# Analog_Modulation_and_Supply.net
KiCad netlist of a schematic drawn in Altium Designer
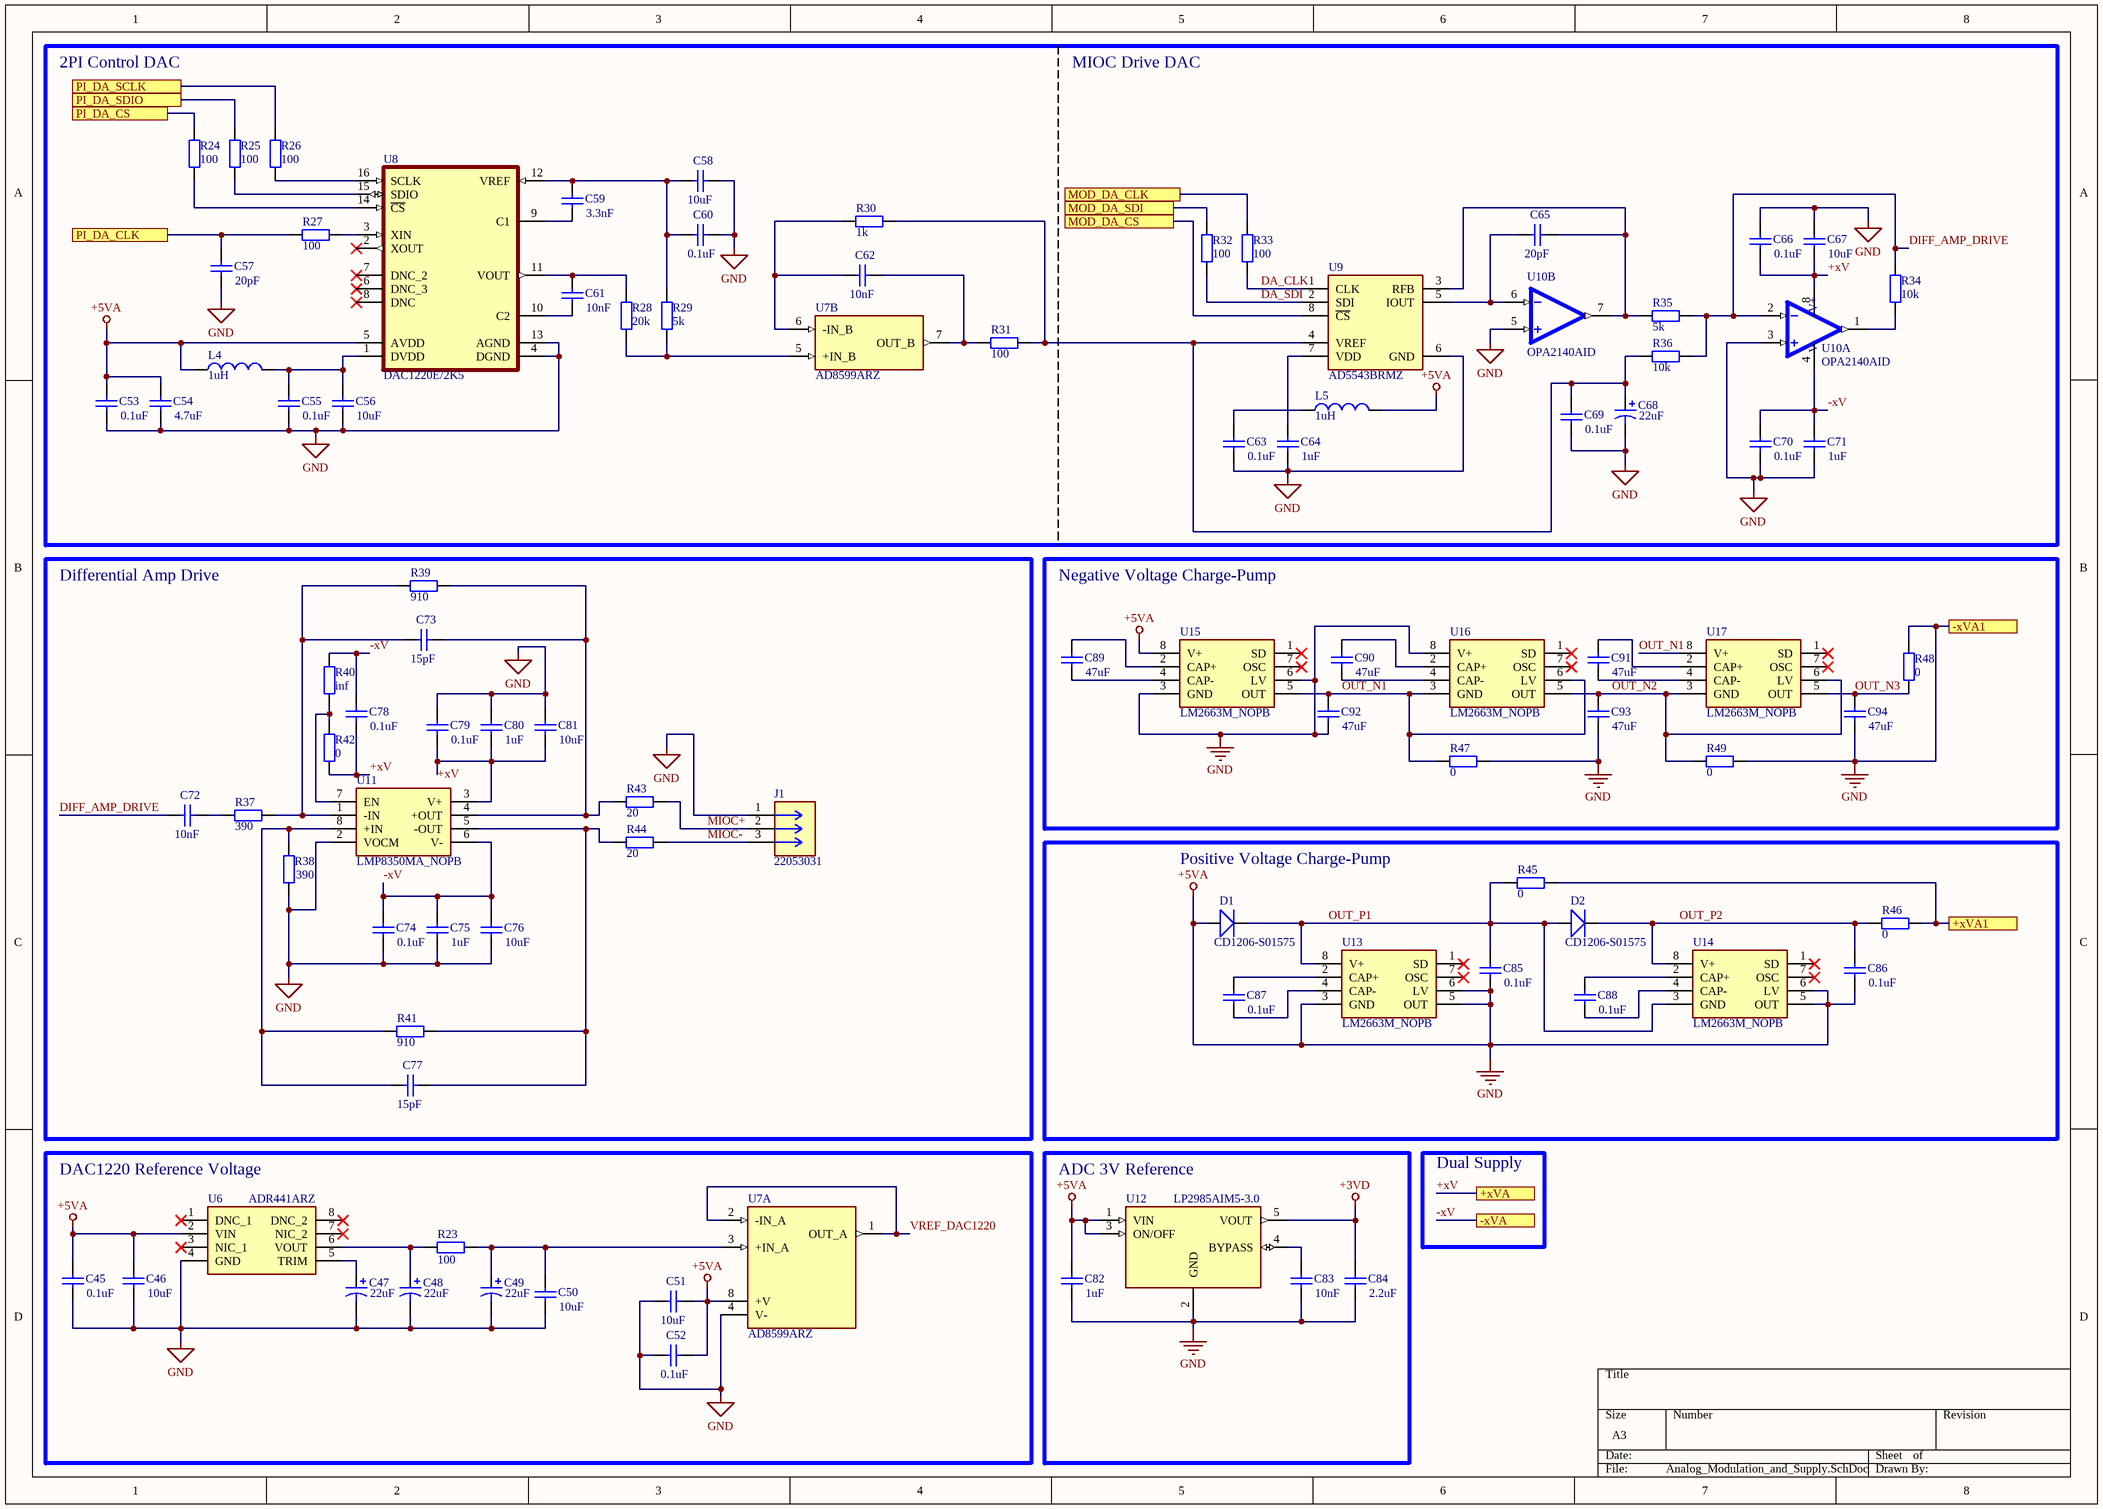
[diagram p0: Analog_Modulation_and_Supply.SchDoc]

(export (version "E")
  (design (tool "Eeschema 10.0.6"))
  (components
    (comp (ref "C45")
      (value "0.1uF")
      (footprint "RAD-0.3")
      (description "Capacitor")
      (fields (field (name "Comment") "Cap") (field (name "PUBLISHER") "Altium Limited"))
      (libsource (lib "Miscellaneous Devices") (part "Cap"))
    )
    (comp (ref "C46")
      (value "10uF")
      (footprint "RAD-0.3")
      (description "Capacitor")
      (fields (field (name "Comment") "Cap") (field (name "PUBLISHER") "Altium Limited"))
      (libsource (lib "Miscellaneous Devices") (part "Cap"))
    )
    (comp (ref "C47")
      (value "22uF")
      (footprint "RB7.6-15")
      (description "Polarized Capacitor (Radial)")
      (fields (field (name "Comment") "Cap Pol1") (field (name "PUBLISHER") "Altium Limited"))
      (libsource (lib "Miscellaneous Devices") (part "Cap Pol1"))
    )
    (comp (ref "C48")
      (value "22uF")
      (footprint "RB7.6-15")
      (description "Polarized Capacitor (Radial)")
      (fields (field (name "Comment") "Cap Pol1") (field (name "PUBLISHER") "Altium Limited"))
      (libsource (lib "Miscellaneous Devices") (part "Cap Pol1"))
    )
    (comp (ref "C49")
      (value "22uF")
      (footprint "RB7.6-15")
      (description "Polarized Capacitor (Radial)")
      (fields (field (name "Comment") "Cap Pol1") (field (name "PUBLISHER") "Altium Limited"))
      (libsource (lib "Miscellaneous Devices") (part "Cap Pol1"))
    )
    (comp (ref "C50")
      (value "10uF")
      (footprint "RAD-0.3")
      (description "Capacitor")
      (fields (field (name "Comment") "Cap") (field (name "PUBLISHER") "Altium Limited"))
      (libsource (lib "Miscellaneous Devices") (part "Cap"))
    )
    (comp (ref "C51")
      (value "10uF")
      (footprint "RAD-0.3")
      (description "Capacitor")
      (fields (field (name "Comment") "Cap") (field (name "PUBLISHER") "Altium Limited"))
      (libsource (lib "Miscellaneous Devices") (part "Cap"))
    )
    (comp (ref "C52")
      (value "0.1uF")
      (footprint "RAD-0.3")
      (description "Capacitor")
      (fields (field (name "Comment") "Cap") (field (name "PUBLISHER") "Altium Limited"))
      (libsource (lib "Miscellaneous Devices") (part "Cap"))
    )
    (comp (ref "C53")
      (value "0.1uF")
      (footprint "RAD-0.3")
      (description "Capacitor")
      (fields (field (name "Comment") "Cap") (field (name "PUBLISHER") "Altium Limited"))
      (libsource (lib "Miscellaneous Devices") (part "Cap"))
    )
    (comp (ref "C54")
      (value "4.7uF")
      (footprint "RAD-0.3")
      (description "Capacitor")
      (fields (field (name "Comment") "Cap") (field (name "PUBLISHER") "Altium Limited"))
      (libsource (lib "Miscellaneous Devices") (part "Cap"))
    )
    (comp (ref "C55")
      (value "0.1uF")
      (footprint "RAD-0.3")
      (description "Capacitor")
      (fields (field (name "Comment") "Cap") (field (name "PUBLISHER") "Altium Limited"))
      (libsource (lib "Miscellaneous Devices") (part "Cap"))
    )
    (comp (ref "C56")
      (value "10uF")
      (footprint "RAD-0.3")
      (description "Capacitor")
      (fields (field (name "Comment") "Cap") (field (name "PUBLISHER") "Altium Limited"))
      (libsource (lib "Miscellaneous Devices") (part "Cap"))
    )
    (comp (ref "C57")
      (value "20pF")
      (footprint "RAD-0.3")
      (description "Capacitor")
      (fields (field (name "Comment") "Cap") (field (name "PUBLISHER") "Altium Limited"))
      (libsource (lib "Miscellaneous Devices") (part "Cap"))
    )
    (comp (ref "C58")
      (value "10uF")
      (footprint "RAD-0.3")
      (description "Capacitor")
      (fields (field (name "Comment") "Cap") (field (name "PUBLISHER") "Altium Limited"))
      (libsource (lib "Miscellaneous Devices") (part "Cap"))
    )
    (comp (ref "C59")
      (value "3.3nF")
      (footprint "RAD-0.3")
      (description "Capacitor")
      (fields (field (name "Comment") "Cap") (field (name "PUBLISHER") "Altium Limited"))
      (libsource (lib "Miscellaneous Devices") (part "Cap"))
    )
    (comp (ref "C60")
      (value "0.1uF")
      (footprint "RAD-0.3")
      (description "Capacitor")
      (fields (field (name "Comment") "Cap") (field (name "PUBLISHER") "Altium Limited"))
      (libsource (lib "Miscellaneous Devices") (part "Cap"))
    )
    (comp (ref "C61")
      (value "10nF")
      (footprint "RAD-0.3")
      (description "Capacitor")
      (fields (field (name "Comment") "Cap") (field (name "PUBLISHER") "Altium Limited"))
      (libsource (lib "Miscellaneous Devices") (part "Cap"))
    )
    (comp (ref "C62")
      (value "10nF")
      (footprint "RAD-0.3")
      (description "Capacitor")
      (fields (field (name "Comment") "Cap") (field (name "PUBLISHER") "Altium Limited"))
      (libsource (lib "Miscellaneous Devices") (part "Cap"))
    )
    (comp (ref "C63")
      (value "0.1uF")
      (footprint "RAD-0.3")
      (description "Capacitor")
      (fields (field (name "Comment") "Cap") (field (name "PUBLISHER") "Altium Limited"))
      (libsource (lib "Miscellaneous Devices") (part "Cap"))
    )
    (comp (ref "C64")
      (value "1uF")
      (footprint "RAD-0.3")
      (description "Capacitor")
      (fields (field (name "Comment") "Cap") (field (name "PUBLISHER") "Altium Limited"))
      (libsource (lib "Miscellaneous Devices") (part "Cap"))
    )
    (comp (ref "C65")
      (value "20pF")
      (footprint "RAD-0.3")
      (description "Capacitor")
      (fields (field (name "Comment") "Cap") (field (name "PUBLISHER") "Altium Limited"))
      (libsource (lib "Miscellaneous Devices") (part "Cap"))
    )
    (comp (ref "C66")
      (value "0.1uF")
      (footprint "RAD-0.3")
      (description "Capacitor")
      (fields (field (name "Comment") "Cap") (field (name "PUBLISHER") "Altium Limited"))
      (libsource (lib "Miscellaneous Devices") (part "Cap"))
    )
    (comp (ref "C67")
      (value "10uF")
      (footprint "RAD-0.3")
      (description "Capacitor")
      (fields (field (name "Comment") "Cap") (field (name "PUBLISHER") "Altium Limited"))
      (libsource (lib "Miscellaneous Devices") (part "Cap"))
    )
    (comp (ref "C68")
      (value "22uF")
      (footprint "RB7.6-15")
      (description "Polarized Capacitor (Radial)")
      (fields (field (name "Comment") "Cap Pol1") (field (name "PUBLISHER") "Altium Limited"))
      (libsource (lib "Miscellaneous Devices") (part "Cap Pol1"))
    )
    (comp (ref "C69")
      (value "0.1uF")
      (footprint "RAD-0.3")
      (description "Capacitor")
      (fields (field (name "Comment") "Cap") (field (name "PUBLISHER") "Altium Limited"))
      (libsource (lib "Miscellaneous Devices") (part "Cap"))
    )
    (comp (ref "C70")
      (value "0.1uF")
      (footprint "RAD-0.3")
      (description "Capacitor")
      (fields (field (name "Comment") "Cap") (field (name "PUBLISHER") "Altium Limited"))
      (libsource (lib "Miscellaneous Devices") (part "Cap"))
    )
    (comp (ref "C71")
      (value "1uF")
      (footprint "RAD-0.3")
      (description "Capacitor")
      (fields (field (name "Comment") "Cap") (field (name "PUBLISHER") "Altium Limited"))
      (libsource (lib "Miscellaneous Devices") (part "Cap"))
    )
    (comp (ref "C72")
      (value "10nF")
      (footprint "RAD-0.3")
      (description "Capacitor")
      (fields (field (name "Comment") "Cap") (field (name "PUBLISHER") "Altium Limited"))
      (libsource (lib "Miscellaneous Devices") (part "Cap"))
    )
    (comp (ref "C73")
      (value "15pF")
      (footprint "RAD-0.3")
      (description "Capacitor")
      (fields (field (name "Comment") "Cap") (field (name "PUBLISHER") "Altium Limited"))
      (libsource (lib "Miscellaneous Devices") (part "Cap"))
    )
    (comp (ref "C74")
      (value "0.1uF")
      (footprint "RAD-0.3")
      (description "Capacitor")
      (fields (field (name "Comment") "Cap") (field (name "PUBLISHER") "Altium Limited"))
      (libsource (lib "Miscellaneous Devices") (part "Cap"))
    )
    (comp (ref "C75")
      (value "1uF")
      (footprint "RAD-0.3")
      (description "Capacitor")
      (fields (field (name "Comment") "Cap") (field (name "PUBLISHER") "Altium Limited"))
      (libsource (lib "Miscellaneous Devices") (part "Cap"))
    )
    (comp (ref "C76")
      (value "10uF")
      (footprint "RAD-0.3")
      (description "Capacitor")
      (fields (field (name "Comment") "Cap") (field (name "PUBLISHER") "Altium Limited"))
      (libsource (lib "Miscellaneous Devices") (part "Cap"))
    )
    (comp (ref "C77")
      (value "15pF")
      (footprint "RAD-0.3")
      (description "Capacitor")
      (fields (field (name "Comment") "Cap") (field (name "PUBLISHER") "Altium Limited"))
      (libsource (lib "Miscellaneous Devices") (part "Cap"))
    )
    (comp (ref "C78")
      (value "0.1uF")
      (footprint "RAD-0.3")
      (description "Capacitor")
      (fields (field (name "Comment") "Cap") (field (name "PUBLISHER") "Altium Limited"))
      (libsource (lib "Miscellaneous Devices") (part "Cap"))
    )
    (comp (ref "C79")
      (value "0.1uF")
      (footprint "RAD-0.3")
      (description "Capacitor")
      (fields (field (name "Comment") "Cap") (field (name "PUBLISHER") "Altium Limited"))
      (libsource (lib "Miscellaneous Devices") (part "Cap"))
    )
    (comp (ref "C80")
      (value "1uF")
      (footprint "RAD-0.3")
      (description "Capacitor")
      (fields (field (name "Comment") "Cap") (field (name "PUBLISHER") "Altium Limited"))
      (libsource (lib "Miscellaneous Devices") (part "Cap"))
    )
    (comp (ref "C81")
      (value "10uF")
      (footprint "RAD-0.3")
      (description "Capacitor")
      (fields (field (name "Comment") "Cap") (field (name "PUBLISHER") "Altium Limited"))
      (libsource (lib "Miscellaneous Devices") (part "Cap"))
    )
    (comp (ref "C82")
      (value "1uF")
      (footprint "RAD-0.3")
      (description "Capacitor")
      (fields (field (name "Comment") "Cap") (field (name "PUBLISHER") "Altium Limited"))
      (libsource (lib "Miscellaneous Devices") (part "Cap"))
    )
    (comp (ref "C83")
      (value "10nF")
      (footprint "RAD-0.3")
      (description "Capacitor")
      (fields (field (name "Comment") "Cap") (field (name "PUBLISHER") "Altium Limited"))
      (libsource (lib "Miscellaneous Devices") (part "Cap"))
    )
    (comp (ref "C84")
      (value "2.2uF")
      (footprint "RAD-0.3")
      (description "Capacitor")
      (fields (field (name "Comment") "Cap") (field (name "PUBLISHER") "Altium Limited"))
      (libsource (lib "Miscellaneous Devices") (part "Cap"))
    )
    (comp (ref "C85")
      (value "0.1uF")
      (footprint "RAD-0.3")
      (description "Capacitor")
      (fields (field (name "Comment") "Cap") (field (name "PUBLISHER") "Altium Limited"))
      (libsource (lib "Miscellaneous Devices") (part "Cap"))
    )
    (comp (ref "C86")
      (value "0.1uF")
      (footprint "RAD-0.3")
      (description "Capacitor")
      (fields (field (name "Comment") "Cap") (field (name "PUBLISHER") "Altium Limited"))
      (libsource (lib "Miscellaneous Devices") (part "Cap"))
    )
    (comp (ref "C87")
      (value "0.1uF")
      (footprint "RAD-0.3")
      (description "Capacitor")
      (fields (field (name "Comment") "Cap") (field (name "PUBLISHER") "Altium Limited"))
      (libsource (lib "Miscellaneous Devices") (part "Cap"))
    )
    (comp (ref "C88")
      (value "0.1uF")
      (footprint "RAD-0.3")
      (description "Capacitor")
      (fields (field (name "Comment") "Cap") (field (name "PUBLISHER") "Altium Limited"))
      (libsource (lib "Miscellaneous Devices") (part "Cap"))
    )
    (comp (ref "C89")
      (value "47uF")
      (footprint "RAD-0.3")
      (description "Capacitor")
      (fields (field (name "Comment") "Cap") (field (name "PUBLISHER") "Altium Limited"))
      (libsource (lib "Miscellaneous Devices") (part "Cap"))
    )
    (comp (ref "C90")
      (value "47uF")
      (footprint "RAD-0.3")
      (description "Capacitor")
      (fields (field (name "Comment") "Cap") (field (name "PUBLISHER") "Altium Limited"))
      (libsource (lib "Miscellaneous Devices") (part "Cap"))
    )
    (comp (ref "C91")
      (value "47uF")
      (footprint "RAD-0.3")
      (description "Capacitor")
      (fields (field (name "Comment") "Cap") (field (name "PUBLISHER") "Altium Limited"))
      (libsource (lib "Miscellaneous Devices") (part "Cap"))
    )
    (comp (ref "C92")
      (value "47uF")
      (footprint "RAD-0.3")
      (description "Capacitor")
      (fields (field (name "Comment") "Cap") (field (name "PUBLISHER") "Altium Limited"))
      (libsource (lib "Miscellaneous Devices") (part "Cap"))
    )
    (comp (ref "C93")
      (value "47uF")
      (footprint "RAD-0.3")
      (description "Capacitor")
      (fields (field (name "Comment") "Cap") (field (name "PUBLISHER") "Altium Limited"))
      (libsource (lib "Miscellaneous Devices") (part "Cap"))
    )
    (comp (ref "C94")
      (value "47uF")
      (footprint "RAD-0.3")
      (description "Capacitor")
      (fields (field (name "Comment") "Cap") (field (name "PUBLISHER") "Altium Limited"))
      (libsource (lib "Miscellaneous Devices") (part "Cap"))
    )
    (comp (ref "D1")
      (value "CD1206-S01575")
      (footprint "LED-1206")
      (description "CD1206-S01575, SMT Switching Diode, Vr=75V 150mA, 4ns, 2-Pin 1206 ¦ Bourns CD1206-S01575")
      (fields (field (name "MF") "Bourns"))
      (libsource (lib "Lib_Schematic_Gyro_Single_Axis") (part "CD1206-S01575"))
    )
    (comp (ref "D2")
      (value "CD1206-S01575")
      (footprint "LED-1206")
      (description "CD1206-S01575, SMT Switching Diode, Vr=75V 150mA, 4ns, 2-Pin 1206 ¦ Bourns CD1206-S01575")
      (fields (field (name "MF") "Bourns"))
      (libsource (lib "Lib_Schematic_Gyro_Single_Axis") (part "CD1206-S01575"))
    )
    (comp (ref "J1")
      (value "22053031")
      (footprint "22-05-3031")
      (description "Headers R/A PCB HDR 3P TIN FRICTION LOCK ¦ Molex Incorporated 22-05-3031")
      (fields (field (name "MF") "Molex") (field (name "MP") "22-05-3031"))
      (libsource (lib "Lib_Schematic_Gyro_Single_Axis") (part "22053031"))
    )
    (comp (ref "L4")
      (value "1uH")
      (footprint "0402-A")
      (description "Inductor")
      (fields (field (name "PUBLISHER") "Altium Limited"))
      (libsource (lib "Miscellaneous Devices") (part "Inductor"))
    )
    (comp (ref "L5")
      (value "1uH")
      (footprint "0402-A")
      (description "Inductor")
      (fields (field (name "PUBLISHER") "Altium Limited"))
      (libsource (lib "Miscellaneous Devices") (part "Inductor"))
    )
    (comp (ref "R23")
      (value "100")
      (footprint "AXIAL-0.4")
      (description "Resistor")
      (fields (field (name "Comment") "Res2") (field (name "PUBLISHER") "Altium Limited"))
      (libsource (lib "") (part "Res2_3"))
    )
    (comp (ref "R24")
      (value "100")
      (footprint "AXIAL-0.4")
      (description "Resistor")
      (fields (field (name "Comment") "Res2") (field (name "PUBLISHER") "Altium Limited"))
      (libsource (lib "") (part "Res2_1"))
    )
    (comp (ref "R25")
      (value "100")
      (footprint "AXIAL-0.4")
      (description "Resistor")
      (fields (field (name "Comment") "Res2") (field (name "PUBLISHER") "Altium Limited"))
      (libsource (lib "") (part "Res2_1"))
    )
    (comp (ref "R26")
      (value "100")
      (footprint "AXIAL-0.4")
      (description "Resistor")
      (fields (field (name "Comment") "Res2") (field (name "PUBLISHER") "Altium Limited"))
      (libsource (lib "") (part "Res2_1"))
    )
    (comp (ref "R27")
      (value "100")
      (footprint "AXIAL-0.4")
      (description "Resistor")
      (fields (field (name "Comment") "Res2") (field (name "PUBLISHER") "Altium Limited"))
      (libsource (lib "Miscellaneous Devices") (part "Res2"))
    )
    (comp (ref "R28")
      (value "20k")
      (footprint "AXIAL-0.4")
      (description "Resistor")
      (fields (field (name "Comment") "Res2") (field (name "PUBLISHER") "Altium Limited"))
      (libsource (lib "") (part "Res2_1"))
    )
    (comp (ref "R29")
      (value "5k")
      (footprint "AXIAL-0.4")
      (description "Resistor")
      (fields (field (name "Comment") "Res2") (field (name "PUBLISHER") "Altium Limited"))
      (libsource (lib "") (part "Res2_1"))
    )
    (comp (ref "R30")
      (value "1k")
      (footprint "AXIAL-0.4")
      (description "Resistor")
      (fields (field (name "Comment") "Res2") (field (name "PUBLISHER") "Altium Limited"))
      (libsource (lib "Miscellaneous Devices") (part "Res2"))
    )
    (comp (ref "R31")
      (value "100")
      (footprint "AXIAL-0.4")
      (description "Resistor")
      (fields (field (name "Comment") "Res2") (field (name "PUBLISHER") "Altium Limited"))
      (libsource (lib "Miscellaneous Devices") (part "Res2"))
    )
    (comp (ref "R32")
      (value "100")
      (footprint "AXIAL-0.4")
      (description "Resistor")
      (fields (field (name "Comment") "Res2") (field (name "PUBLISHER") "Altium Limited"))
      (libsource (lib "") (part "Res2_2"))
    )
    (comp (ref "R33")
      (value "100")
      (footprint "AXIAL-0.4")
      (description "Resistor")
      (fields (field (name "Comment") "Res2") (field (name "PUBLISHER") "Altium Limited"))
      (libsource (lib "") (part "Res2_2"))
    )
    (comp (ref "R34")
      (value "10k")
      (footprint "AXIAL-0.4")
      (description "Resistor")
      (fields (field (name "Comment") "Res2") (field (name "PUBLISHER") "Altium Limited"))
      (libsource (lib "") (part "Res2_2"))
    )
    (comp (ref "R35")
      (value "5k")
      (footprint "AXIAL-0.4")
      (description "Resistor")
      (fields (field (name "Comment") "Res2") (field (name "PUBLISHER") "Altium Limited"))
      (libsource (lib "Miscellaneous Devices") (part "Res2"))
    )
    (comp (ref "R36")
      (value "10k")
      (footprint "AXIAL-0.4")
      (description "Resistor")
      (fields (field (name "Comment") "Res2") (field (name "PUBLISHER") "Altium Limited"))
      (libsource (lib "Miscellaneous Devices") (part "Res2"))
    )
    (comp (ref "R37")
      (value "390")
      (footprint "AXIAL-0.4")
      (description "Resistor")
      (fields (field (name "Comment") "Res2") (field (name "PUBLISHER") "Altium Limited"))
      (libsource (lib "Miscellaneous Devices") (part "Res2"))
    )
    (comp (ref "R38")
      (value "390")
      (footprint "AXIAL-0.4")
      (description "Resistor")
      (fields (field (name "Comment") "Res2") (field (name "PUBLISHER") "Altium Limited"))
      (libsource (lib "") (part "Res2_2"))
    )
    (comp (ref "R39")
      (value "910")
      (footprint "AXIAL-0.4")
      (description "Resistor")
      (fields (field (name "Comment") "Res2") (field (name "PUBLISHER") "Altium Limited"))
      (libsource (lib "Miscellaneous Devices") (part "Res2"))
    )
    (comp (ref "R40")
      (value "inf")
      (footprint "AXIAL-0.4")
      (description "Resistor")
      (fields (field (name "Comment") "Res2") (field (name "PUBLISHER") "Altium Limited"))
      (libsource (lib "") (part "Res2_2"))
    )
    (comp (ref "R41")
      (value "910")
      (footprint "AXIAL-0.4")
      (description "Resistor")
      (fields (field (name "Comment") "Res2") (field (name "PUBLISHER") "Altium Limited"))
      (libsource (lib "Miscellaneous Devices") (part "Res2"))
    )
    (comp (ref "R42")
      (value "0")
      (footprint "AXIAL-0.4")
      (description "Resistor")
      (fields (field (name "Comment") "Res2") (field (name "PUBLISHER") "Altium Limited"))
      (libsource (lib "") (part "Res2_2"))
    )
    (comp (ref "R43")
      (value "20")
      (footprint "AXIAL-0.4")
      (description "Resistor")
      (fields (field (name "Comment") "Res2") (field (name "PUBLISHER") "Altium Limited"))
      (libsource (lib "Miscellaneous Devices") (part "Res2"))
    )
    (comp (ref "R44")
      (value "20")
      (footprint "AXIAL-0.4")
      (description "Resistor")
      (fields (field (name "Comment") "Res2") (field (name "PUBLISHER") "Altium Limited"))
      (libsource (lib "Miscellaneous Devices") (part "Res2"))
    )
    (comp (ref "R45")
      (value "0")
      (footprint "AXIAL-0.4")
      (description "Resistor")
      (fields (field (name "Comment") "Res2") (field (name "PUBLISHER") "Altium Limited"))
      (libsource (lib "Miscellaneous Devices") (part "Res2"))
    )
    (comp (ref "R46")
      (value "0")
      (footprint "AXIAL-0.4")
      (description "Resistor")
      (fields (field (name "Comment") "Res2") (field (name "PUBLISHER") "Altium Limited"))
      (libsource (lib "Miscellaneous Devices") (part "Res2"))
    )
    (comp (ref "R47")
      (value "0")
      (footprint "AXIAL-0.4")
      (description "Resistor")
      (fields (field (name "Comment") "Res2") (field (name "PUBLISHER") "Altium Limited"))
      (libsource (lib "Miscellaneous Devices") (part "Res2"))
    )
    (comp (ref "R48")
      (value "0")
      (footprint "AXIAL-0.4")
      (description "Resistor")
      (fields (field (name "Comment") "Res2") (field (name "PUBLISHER") "Altium Limited"))
      (libsource (lib "") (part "Res2_2"))
    )
    (comp (ref "R49")
      (value "0")
      (footprint "AXIAL-0.4")
      (description "Resistor")
      (fields (field (name "Comment") "Res2") (field (name "PUBLISHER") "Altium Limited"))
      (libsource (lib "Miscellaneous Devices") (part "Res2"))
    )
    (comp (ref "U6")
      (value "ADR441ARZ")
      (footprint "SOIC127P600X175-8N")
      (description "Series Voltage Reference IC Fixed 2.5V V +/-0.12% 10 mA 8-SOIC")
      (fields (field (name "MOUSER PART NUMBER") "584-ADR441ARZ"))
      (libsource (lib "Lib_Schematic_Gyro_Single_Axis") (part "ADR441ARZ"))
    )
    (comp (ref "U7")
      (value "AD8599ARZ")
      (footprint "AD8599ARZ")
      (description "Ultralow Distortion, Ultralow Noise Op Amp (Dual)")
      (fields (field (name "MF") "Analog Devices"))
      (libsource (lib "Lib_Schematic_Gyro_Single_Axis") (part "AD8599ARZ"))
    )
    (comp (ref "U8")
      (value "DAC1220E/2K5")
      (footprint "DAC1220E/2K5")
      (description "Digital-to-Analog Converter")
      (libsource (lib "Lib_Schematic_Gyro_Single_Axis") (part "DAC1220E/2K5"))
    )
    (comp (ref "U9")
      (value "AD5543BRMZ")
      (footprint "SOP65P490X110-8N")
      (description "AD5543BRMZ, 16-Bit General Purpose DAC 2.47Msps, SPI, 8-Pin MSOP")
      (fields (field (name "MOUSER PART NUMBER") "584-AD5543BRMZ"))
      (libsource (lib "Lib_Schematic_Gyro_Single_Axis") (part "AD5543BRMZ"))
    )
    (comp (ref "U10")
      (value "OPA2140AID")
      (footprint "OPA2140AID")
      (description "Dual-channel, 11-MHz, low-noise 36-V JFET precision operational amplifier with rail-to-rail output")
      (fields (field (name "MF") "Texas Instruments"))
      (libsource (lib "Lib_Schematic_Gyro_Single_Axis") (part "OPA2140AID"))
    )
    (comp (ref "U11")
      (value "LMP8350MA_NOPB")
      (footprint "LMP8350MA_NOPB")
      (description "Ultra Low Distortion Fully Differential Precision ADC Driver with Selectable Power Modes")
      (fields
        (field (name "MANUFACTURER_PART_NUMBER") "LMP8350MA/NOPB")
        (field (name "MOUSER PART NUMBER") "926-LMP8350MA/NOPB")
      )
      (libsource (lib "Lib_Schematic_Gyro_Single_Axis") (part "LMP8350MA_NOPB"))
    )
    (comp (ref "U12")
      (value "LP2985AIM5-3.0")
      (footprint "LP2985AIM5-3.0")
      (description "150-mA, 16-V, low-dropout voltage regulator with enable")
      (fields (field (name "MF") "Texas Instruments") (field (name "MP") "LP2985AIM5-3.0/NOPB"))
      (libsource (lib "Lib_Schematic_Gyro_Single_Axis") (part "LP2985AIM5-3.0"))
    )
    (comp (ref "U13")
      (value "LM2663M_NOPB")
      (footprint "LM2663M_NOPB")
      (description "200mA switched capacitor voltage converter with low current shutdown mode")
      (fields
        (field (name "MANUFACTURER_PART_NUMBER") "LM2663M/NOPB")
        (field (name "MOUSER PART NUMBER") "926-LM2663M/NOPB")
      )
      (libsource (lib "Lib_Schematic_Gyro_Single_Axis") (part "LM2663M_NOPB"))
    )
    (comp (ref "U14")
      (value "LM2663M_NOPB")
      (footprint "LM2663M_NOPB")
      (description "200mA switched capacitor voltage converter with low current shutdown mode")
      (fields
        (field (name "MANUFACTURER_PART_NUMBER") "LM2663M/NOPB")
        (field (name "MOUSER PART NUMBER") "926-LM2663M/NOPB")
      )
      (libsource (lib "Lib_Schematic_Gyro_Single_Axis") (part "LM2663M_NOPB"))
    )
    (comp (ref "U15")
      (value "LM2663M_NOPB")
      (footprint "LM2663M_NOPB")
      (description "200mA switched capacitor voltage converter with low current shutdown mode")
      (fields
        (field (name "MANUFACTURER_PART_NUMBER") "LM2663M/NOPB")
        (field (name "MOUSER PART NUMBER") "926-LM2663M/NOPB")
      )
      (libsource (lib "Lib_Schematic_Gyro_Single_Axis") (part "LM2663M_NOPB"))
    )
    (comp (ref "U16")
      (value "LM2663M_NOPB")
      (footprint "LM2663M_NOPB")
      (description "200mA switched capacitor voltage converter with low current shutdown mode")
      (fields
        (field (name "MANUFACTURER_PART_NUMBER") "LM2663M/NOPB")
        (field (name "MOUSER PART NUMBER") "926-LM2663M/NOPB")
      )
      (libsource (lib "Lib_Schematic_Gyro_Single_Axis") (part "LM2663M_NOPB"))
    )
    (comp (ref "U17")
      (value "LM2663M_NOPB")
      (footprint "LM2663M_NOPB")
      (description "200mA switched capacitor voltage converter with low current shutdown mode")
      (fields
        (field (name "MANUFACTURER_PART_NUMBER") "LM2663M/NOPB")
        (field (name "MOUSER PART NUMBER") "926-LM2663M/NOPB")
      )
      (libsource (lib "Lib_Schematic_Gyro_Single_Axis") (part "LM2663M_NOPB"))
    )
  )
  (nets
    (net (code "1") (name "+3VD") (class "Default")
      (node (ref "C84") (pin "1") (pinfunction "1_1") (pintype "passive"))
      (node (ref "U12") (pin "5") (pinfunction "VOUT_5") (pintype "output"))
    )
    (net (code "2") (name "+5VA") (class "Default")
      (node (ref "C45") (pin "1") (pinfunction "1_1") (pintype "passive"))
      (node (ref "C45") (pin "2") (pinfunction "2_2") (pintype "passive"))
      (node (ref "C46") (pin "1") (pinfunction "1_1") (pintype "passive"))
      (node (ref "C46") (pin "2") (pinfunction "2_2") (pintype "passive"))
      (node (ref "C47") (pin "2") (pinfunction "2_2") (pintype "passive"))
      (node (ref "C48") (pin "2") (pinfunction "2_2") (pintype "passive"))
      (node (ref "C49") (pin "2") (pinfunction "2_2") (pintype "passive"))
      (node (ref "C50") (pin "1") (pinfunction "1_1") (pintype "passive"))
      (node (ref "C51") (pin "1") (pinfunction "1_1") (pintype "passive"))
      (node (ref "C51") (pin "2") (pinfunction "2_2") (pintype "passive"))
      (node (ref "C52") (pin "1") (pinfunction "1_1") (pintype "passive"))
      (node (ref "C52") (pin "2") (pinfunction "2_2") (pintype "passive"))
      (node (ref "C53") (pin "1") (pinfunction "1_1") (pintype "passive"))
      (node (ref "C53") (pin "2") (pinfunction "2_2") (pintype "passive"))
      (node (ref "C54") (pin "1") (pinfunction "1_1") (pintype "passive"))
      (node (ref "C54") (pin "2") (pinfunction "2_2") (pintype "passive"))
      (node (ref "C55") (pin "2") (pinfunction "2_2") (pintype "passive"))
      (node (ref "C56") (pin "2") (pinfunction "2_2") (pintype "passive"))
      (node (ref "C57") (pin "2") (pinfunction "2_2") (pintype "passive"))
      (node (ref "C58") (pin "1") (pinfunction "1_1") (pintype "passive"))
      (node (ref "C60") (pin "1") (pinfunction "1_1") (pintype "passive"))
      (node (ref "C63") (pin "2") (pinfunction "2_2") (pintype "passive"))
      (node (ref "C64") (pin "2") (pinfunction "2_2") (pintype "passive"))
      (node (ref "C66") (pin "1") (pinfunction "1_1") (pintype "passive"))
      (node (ref "C67") (pin "1") (pinfunction "1_1") (pintype "passive"))
      (node (ref "C68") (pin "2") (pinfunction "2_2") (pintype "passive"))
      (node (ref "C69") (pin "1") (pinfunction "1_1") (pintype "passive"))
      (node (ref "C70") (pin "2") (pinfunction "2_2") (pintype "passive"))
      (node (ref "C71") (pin "2") (pinfunction "2_2") (pintype "passive"))
      (node (ref "C74") (pin "2") (pinfunction "2_2") (pintype "passive"))
      (node (ref "C75") (pin "2") (pinfunction "2_2") (pintype "passive"))
      (node (ref "C76") (pin "2") (pinfunction "2_2") (pintype "passive"))
      (node (ref "C79") (pin "1") (pinfunction "1_1") (pintype "passive"))
      (node (ref "C80") (pin "1") (pinfunction "1_1") (pintype "passive"))
      (node (ref "C81") (pin "1") (pinfunction "1_1") (pintype "passive"))
      (node (ref "C82") (pin "1") (pinfunction "1_1") (pintype "passive"))
      (node (ref "C82") (pin "2") (pinfunction "2_2") (pintype "passive"))
      (node (ref "C83") (pin "2") (pinfunction "2_2") (pintype "passive"))
      (node (ref "C84") (pin "2") (pinfunction "2_2") (pintype "passive"))
      (node (ref "C85") (pin "2") (pinfunction "2_2") (pintype "passive"))
      (node (ref "C86") (pin "2") (pinfunction "2_2") (pintype "passive"))
      (node (ref "C92") (pin "2") (pinfunction "2_2") (pintype "passive"))
      (node (ref "C93") (pin "2") (pinfunction "2_2") (pintype "passive"))
      (node (ref "C94") (pin "2") (pinfunction "2_2") (pintype "passive"))
      (node (ref "D1") (pin "POS") (pinfunction "POS_POS") (pintype "passive"))
      (node (ref "J1") (pin "1") (pinfunction "1_1") (pintype "passive"))
      (node (ref "L4") (pin "1") (pinfunction "1_1") (pintype "passive"))
      (node (ref "L5") (pin "2") (pinfunction "2_2") (pintype "passive"))
      (node (ref "R38") (pin "2") (pinfunction "2_2") (pintype "passive"))
      (node (ref "R47") (pin "1") (pinfunction "1_1") (pintype "passive"))
      (node (ref "R48") (pin "1") (pinfunction "1_1") (pintype "passive"))
      (node (ref "R49") (pin "1") (pinfunction "1_1") (pintype "passive"))
      (node (ref "U10") (pin "3") (pinfunction "+INA_3") (pintype "input"))
      (node (ref "U10") (pin "5") (pinfunction "+INB_5") (pintype "input"))
      (node (ref "U11") (pin "2") (pinfunction "VOCM_2") (pintype "passive"))
      (node (ref "U12") (pin "1") (pinfunction "VIN_1") (pintype "input"))
      (node (ref "U12") (pin "2") (pinfunction "GND_2") (pintype "power_in"))
      (node (ref "U12") (pin "3") (pinfunction "ON/OFF_3") (pintype "input"))
      (node (ref "U13") (pin "3") (pinfunction "GND_3") (pintype "passive"))
      (node (ref "U13") (pin "5") (pinfunction "OUT_5") (pintype "passive"))
      (node (ref "U13") (pin "6") (pinfunction "LV_6") (pintype "passive"))
      (node (ref "U14") (pin "5") (pinfunction "OUT_5") (pintype "passive"))
      (node (ref "U14") (pin "6") (pinfunction "LV_6") (pintype "passive"))
      (node (ref "U15") (pin "3") (pinfunction "GND_3") (pintype "passive"))
      (node (ref "U15") (pin "6") (pinfunction "LV_6") (pintype "passive"))
      (node (ref "U15") (pin "8") (pinfunction "V+_8") (pintype "passive"))
      (node (ref "U16") (pin "8") (pinfunction "V+_8") (pintype "passive"))
      (node (ref "U6") (pin "2") (pinfunction "VIN_2") (pintype "passive"))
      (node (ref "U6") (pin "4") (pinfunction "GND_4") (pintype "passive"))
      (node (ref "U7") (pin "4") (pinfunction "V-_4") (pintype "power_in"))
      (node (ref "U7") (pin "8") (pinfunction "+V_8") (pintype "power_in"))
      (node (ref "U8") (pin "13") (pinfunction "AGND_13") (pintype "passive"))
      (node (ref "U8") (pin "4") (pinfunction "DGND_4") (pintype "passive"))
      (node (ref "U8") (pin "5") (pinfunction "AVDD_5") (pintype "power_in"))
      (node (ref "U9") (pin "6") (pinfunction "GND_6") (pintype "passive"))
    )
    (net (code "3") (name "/+xV") (class "Default")
      (node (ref "C66") (pin "2") (pinfunction "2_2") (pintype "passive"))
      (node (ref "C67") (pin "2") (pinfunction "2_2") (pintype "passive"))
      (node (ref "C78") (pin "2") (pinfunction "2_2") (pintype "passive"))
      (node (ref "R42") (pin "2") (pinfunction "2_2") (pintype "passive"))
      (node (ref "U10") (pin "8") (pinfunction "V+_8") (pintype "power_in"))
    )
    (net (code "4") (name "/+xVA1") (class "Default")
      (node (ref "R45") (pin "1") (pinfunction "1_1") (pintype "passive"))
      (node (ref "R46") (pin "1") (pinfunction "1_1") (pintype "passive"))
    )
    (net (code "5") (name "/-xV") (class "Default")
      (node (ref "C70") (pin "1") (pinfunction "1_1") (pintype "passive"))
      (node (ref "C71") (pin "1") (pinfunction "1_1") (pintype "passive"))
      (node (ref "C74") (pin "1") (pinfunction "1_1") (pintype "passive"))
      (node (ref "C75") (pin "1") (pinfunction "1_1") (pintype "passive"))
      (node (ref "C76") (pin "1") (pinfunction "1_1") (pintype "passive"))
      (node (ref "C78") (pin "1") (pinfunction "1_1") (pintype "passive"))
      (node (ref "R40") (pin "1") (pinfunction "1_1") (pintype "passive"))
      (node (ref "U10") (pin "4") (pinfunction "V-_4") (pintype "power_in"))
      (node (ref "U11") (pin "6") (pinfunction "V-_6") (pintype "passive"))
    )
    (net (code "6") (name "/DA_CLK") (class "Default")
      (node (ref "R33") (pin "2") (pinfunction "2_2") (pintype "passive"))
      (node (ref "U9") (pin "1") (pinfunction "CLK_1") (pintype "passive"))
    )
    (net (code "7") (name "/DA_SDI") (class "Default")
      (node (ref "R32") (pin "2") (pinfunction "2_2") (pintype "passive"))
      (node (ref "U9") (pin "2") (pinfunction "SDI_2") (pintype "passive"))
    )
    (net (code "8") (name "/DIFF_AMP_DRIVE") (class "Default")
      (node (ref "C72") (pin "2") (pinfunction "2_2") (pintype "passive"))
      (node (ref "R34") (pin "1") (pinfunction "1_1") (pintype "passive"))
      (node (ref "R35") (pin "1") (pinfunction "1_1") (pintype "passive"))
      (node (ref "R36") (pin "1") (pinfunction "1_1") (pintype "passive"))
      (node (ref "U10") (pin "2") (pinfunction "-INA_2") (pintype "input"))
    )
    (net (code "9") (name "/MIOC+") (class "Default")
      (node (ref "J1") (pin "2") (pinfunction "2_2") (pintype "passive"))
      (node (ref "R43") (pin "1") (pinfunction "1_1") (pintype "passive"))
    )
    (net (code "10") (name "/MIOC-") (class "Default")
      (node (ref "J1") (pin "3") (pinfunction "3_3") (pintype "passive"))
      (node (ref "R44") (pin "1") (pinfunction "1_1") (pintype "passive"))
    )
    (net (code "11") (name "/MOD_DA_CLK") (class "Default")
      (node (ref "R33") (pin "1") (pinfunction "1_1") (pintype "passive"))
    )
    (net (code "12") (name "/MOD_DA_CS") (class "Default")
      (node (ref "U9") (pin "8") (pinfunction "~{CS}_8") (pintype "passive"))
    )
    (net (code "13") (name "/MOD_DA_SDI") (class "Default")
      (node (ref "R32") (pin "1") (pinfunction "1_1") (pintype "passive"))
    )
    (net (code "14") (name "/OUT_N1") (class "Default")
      (node (ref "C92") (pin "1") (pinfunction "1_1") (pintype "passive"))
      (node (ref "R47") (pin "2") (pinfunction "2_2") (pintype "passive"))
      (node (ref "U15") (pin "5") (pinfunction "OUT_5") (pintype "passive"))
      (node (ref "U16") (pin "3") (pinfunction "GND_3") (pintype "passive"))
      (node (ref "U16") (pin "6") (pinfunction "LV_6") (pintype "passive"))
      (node (ref "U17") (pin "8") (pinfunction "V+_8") (pintype "passive"))
    )
    (net (code "15") (name "/OUT_N2") (class "Default")
      (node (ref "C93") (pin "1") (pinfunction "1_1") (pintype "passive"))
      (node (ref "R49") (pin "2") (pinfunction "2_2") (pintype "passive"))
      (node (ref "U16") (pin "5") (pinfunction "OUT_5") (pintype "passive"))
      (node (ref "U17") (pin "3") (pinfunction "GND_3") (pintype "passive"))
      (node (ref "U17") (pin "6") (pinfunction "LV_6") (pintype "passive"))
    )
    (net (code "16") (name "/OUT_N3") (class "Default")
      (node (ref "C94") (pin "1") (pinfunction "1_1") (pintype "passive"))
      (node (ref "R48") (pin "2") (pinfunction "2_2") (pintype "passive"))
      (node (ref "U17") (pin "5") (pinfunction "OUT_5") (pintype "passive"))
    )
    (net (code "17") (name "/OUT_P1") (class "Default")
      (node (ref "C85") (pin "1") (pinfunction "1_1") (pintype "passive"))
      (node (ref "D1") (pin "NEG") (pinfunction "NEG_NEG") (pintype "passive"))
      (node (ref "D2") (pin "POS") (pinfunction "POS_POS") (pintype "passive"))
      (node (ref "R45") (pin "2") (pinfunction "2_2") (pintype "passive"))
      (node (ref "U13") (pin "8") (pinfunction "V+_8") (pintype "passive"))
      (node (ref "U14") (pin "3") (pinfunction "GND_3") (pintype "passive"))
    )
    (net (code "18") (name "/OUT_P2") (class "Default")
      (node (ref "C86") (pin "1") (pinfunction "1_1") (pintype "passive"))
      (node (ref "D2") (pin "NEG") (pinfunction "NEG_NEG") (pintype "passive"))
      (node (ref "R46") (pin "2") (pinfunction "2_2") (pintype "passive"))
      (node (ref "U14") (pin "8") (pinfunction "V+_8") (pintype "passive"))
    )
    (net (code "19") (name "/PI_DA_CLK") (class "Default")
      (node (ref "C57") (pin "1") (pinfunction "1_1") (pintype "passive"))
      (node (ref "R27") (pin "2") (pinfunction "2_2") (pintype "passive"))
    )
    (net (code "20") (name "/PI_DA_CS") (class "Default")
      (node (ref "R24") (pin "2") (pinfunction "2_2") (pintype "passive"))
    )
    (net (code "21") (name "/PI_DA_SCLK") (class "Default")
      (node (ref "R26") (pin "2") (pinfunction "2_2") (pintype "passive"))
    )
    (net (code "22") (name "/PI_DA_SDIO") (class "Default")
      (node (ref "R25") (pin "2") (pinfunction "2_2") (pintype "passive"))
    )
    (net (code "23") (name "/VREF_DAC1220") (class "Default")
      (node (ref "U7") (pin "1") (pinfunction "OUT_A_1") (pintype "output"))
      (node (ref "U7") (pin "2") (pinfunction "-IN_A_2") (pintype "input"))
    )
    (net (code "24") (name "Net-(C63-Pad1)") (class "Default")
      (node (ref "C63") (pin "1") (pinfunction "1_1") (pintype "passive"))
      (node (ref "L5") (pin "1") (pinfunction "1_1") (pintype "passive"))
    )
    (net (code "25") (name "Net-(C72-Pad1)") (class "Default")
      (node (ref "C72") (pin "1") (pinfunction "1_1") (pintype "passive"))
      (node (ref "R37") (pin "2") (pinfunction "2_2") (pintype "passive"))
    )
    (net (code "26") (name "Net-(U6-TRIM)") (class "Default")
      (node (ref "C47") (pin "1") (pinfunction "1_1") (pintype "passive"))
      (node (ref "U6") (pin "5") (pinfunction "TRIM_5") (pintype "passive"))
    )
    (net (code "27") (name "Net-(U6-VOUT)") (class "Default")
      (node (ref "C48") (pin "1") (pinfunction "1_1") (pintype "passive"))
      (node (ref "R23") (pin "1") (pinfunction "1_1") (pintype "passive"))
      (node (ref "U6") (pin "6") (pinfunction "VOUT_6") (pintype "passive"))
    )
    (net (code "28") (name "Net-(U7A-+IN_A)") (class "Default")
      (node (ref "C49") (pin "1") (pinfunction "1_1") (pintype "passive"))
      (node (ref "C50") (pin "2") (pinfunction "2_2") (pintype "passive"))
      (node (ref "R23") (pin "2") (pinfunction "2_2") (pintype "passive"))
      (node (ref "U7") (pin "3") (pinfunction "+IN_A_3") (pintype "input"))
    )
    (net (code "29") (name "Net-(U7B-+IN_B)") (class "Default")
      (node (ref "R28") (pin "1") (pinfunction "1_1") (pintype "passive"))
      (node (ref "R29") (pin "1") (pinfunction "1_1") (pintype "passive"))
      (node (ref "U7") (pin "5") (pinfunction "+IN_B_5") (pintype "input"))
    )
    (net (code "30") (name "Net-(U7B--IN_B)") (class "Default")
      (node (ref "C62") (pin "2") (pinfunction "2_2") (pintype "passive"))
      (node (ref "R30") (pin "2") (pinfunction "2_2") (pintype "passive"))
      (node (ref "U7") (pin "6") (pinfunction "-IN_B_6") (pintype "input"))
    )
    (net (code "31") (name "Net-(U7B-OUT_B)") (class "Default")
      (node (ref "C62") (pin "1") (pinfunction "1_1") (pintype "passive"))
      (node (ref "R31") (pin "2") (pinfunction "2_2") (pintype "passive"))
      (node (ref "U7") (pin "7") (pinfunction "OUT_B_7") (pintype "output"))
    )
    (net (code "32") (name "Net-(U8-C1)") (class "Default")
      (node (ref "C59") (pin "2") (pinfunction "2_2") (pintype "passive"))
      (node (ref "U8") (pin "9") (pinfunction "C1_9") (pintype "passive"))
    )
    (net (code "33") (name "Net-(U8-C2)") (class "Default")
      (node (ref "C61") (pin "2") (pinfunction "2_2") (pintype "passive"))
      (node (ref "U8") (pin "10") (pinfunction "C2_10") (pintype "passive"))
    )
    (net (code "34") (name "Net-(U8-DVDD)") (class "Default")
      (node (ref "C55") (pin "1") (pinfunction "1_1") (pintype "passive"))
      (node (ref "C56") (pin "1") (pinfunction "1_1") (pintype "passive"))
      (node (ref "L4") (pin "2") (pinfunction "2_2") (pintype "passive"))
      (node (ref "U8") (pin "1") (pinfunction "DVDD_1") (pintype "power_in"))
    )
    (net (code "35") (name "Net-(U8-SCLK)") (class "Default")
      (node (ref "R26") (pin "1") (pinfunction "1_1") (pintype "passive"))
      (node (ref "U8") (pin "16") (pinfunction "SCLK_16") (pintype "input"))
    )
    (net (code "36") (name "Net-(U8-SDIO)") (class "Default")
      (node (ref "R25") (pin "1") (pinfunction "1_1") (pintype "passive"))
      (node (ref "U8") (pin "15") (pinfunction "SDIO_15") (pintype "bidirectional"))
    )
    (net (code "37") (name "Net-(U8-VOUT)") (class "Default")
      (node (ref "C61") (pin "1") (pinfunction "1_1") (pintype "passive"))
      (node (ref "R28") (pin "2") (pinfunction "2_2") (pintype "passive"))
      (node (ref "U8") (pin "11") (pinfunction "VOUT_11") (pintype "output"))
    )
    (net (code "38") (name "Net-(U8-VREF)") (class "Default")
      (node (ref "C58") (pin "2") (pinfunction "2_2") (pintype "passive"))
      (node (ref "C59") (pin "1") (pinfunction "1_1") (pintype "passive"))
      (node (ref "C60") (pin "2") (pinfunction "2_2") (pintype "passive"))
      (node (ref "R29") (pin "2") (pinfunction "2_2") (pintype "passive"))
      (node (ref "U8") (pin "12") (pinfunction "VREF_12") (pintype "input"))
    )
    (net (code "39") (name "Net-(U8-XIN)") (class "Default")
      (node (ref "R27") (pin "1") (pinfunction "1_1") (pintype "passive"))
      (node (ref "U8") (pin "3") (pinfunction "XIN_3") (pintype "input"))
    )
    (net (code "40") (name "Net-(U8-~{CS})") (class "Default")
      (node (ref "R24") (pin "1") (pinfunction "1_1") (pintype "passive"))
      (node (ref "U8") (pin "14") (pinfunction "~{CS}_14") (pintype "input"))
    )
    (net (code "41") (name "Net-(U9-VDD)") (class "Default")
      (node (ref "C64") (pin "1") (pinfunction "1_1") (pintype "passive"))
      (node (ref "U9") (pin "7") (pinfunction "VDD_7") (pintype "passive"))
    )
    (net (code "42") (name "Net-(U9-VREF)") (class "Default")
      (node (ref "C68") (pin "1") (pinfunction "1_1") (pintype "passive"))
      (node (ref "C69") (pin "2") (pinfunction "2_2") (pintype "passive"))
      (node (ref "R30") (pin "1") (pinfunction "1_1") (pintype "passive"))
      (node (ref "R31") (pin "1") (pinfunction "1_1") (pintype "passive"))
      (node (ref "R36") (pin "2") (pinfunction "2_2") (pintype "passive"))
      (node (ref "U9") (pin "4") (pinfunction "VREF_4") (pintype "passive"))
    )
    (net (code "43") (name "Net-(U10A-OUTA)") (class "Default")
      (node (ref "R34") (pin "2") (pinfunction "2_2") (pintype "passive"))
      (node (ref "U10") (pin "1") (pinfunction "OUTA_1") (pintype "output"))
    )
    (net (code "44") (name "Net-(U10B--INB)") (class "Default")
      (node (ref "C65") (pin "2") (pinfunction "2_2") (pintype "passive"))
      (node (ref "U10") (pin "6") (pinfunction "-INB_6") (pintype "input"))
      (node (ref "U9") (pin "5") (pinfunction "IOUT_5") (pintype "passive"))
    )
    (net (code "45") (name "Net-(U10B-OUTB)") (class "Default")
      (node (ref "C65") (pin "1") (pinfunction "1_1") (pintype "passive"))
      (node (ref "R35") (pin "2") (pinfunction "2_2") (pintype "passive"))
      (node (ref "U10") (pin "7") (pinfunction "OUTB_7") (pintype "output"))
      (node (ref "U9") (pin "3") (pinfunction "RFB_3") (pintype "passive"))
    )
    (net (code "46") (name "Net-(U11-+IN)") (class "Default")
      (node (ref "C77") (pin "2") (pinfunction "2_2") (pintype "passive"))
      (node (ref "R38") (pin "1") (pinfunction "1_1") (pintype "passive"))
      (node (ref "R41") (pin "2") (pinfunction "2_2") (pintype "passive"))
      (node (ref "U11") (pin "8") (pinfunction "+IN_8") (pintype "passive"))
    )
    (net (code "47") (name "Net-(U11-+OUT)") (class "Default")
      (node (ref "C73") (pin "1") (pinfunction "1_1") (pintype "passive"))
      (node (ref "R39") (pin "1") (pinfunction "1_1") (pintype "passive"))
      (node (ref "R43") (pin "2") (pinfunction "2_2") (pintype "passive"))
      (node (ref "U11") (pin "4") (pinfunction "+OUT_4") (pintype "passive"))
    )
    (net (code "48") (name "Net-(U11--IN)") (class "Default")
      (node (ref "C73") (pin "2") (pinfunction "2_2") (pintype "passive"))
      (node (ref "R37") (pin "1") (pinfunction "1_1") (pintype "passive"))
      (node (ref "R39") (pin "2") (pinfunction "2_2") (pintype "passive"))
      (node (ref "U11") (pin "1") (pinfunction "-IN_1") (pintype "passive"))
    )
    (net (code "49") (name "Net-(U11--OUT)") (class "Default")
      (node (ref "C77") (pin "1") (pinfunction "1_1") (pintype "passive"))
      (node (ref "R41") (pin "1") (pinfunction "1_1") (pintype "passive"))
      (node (ref "R44") (pin "2") (pinfunction "2_2") (pintype "passive"))
      (node (ref "U11") (pin "5") (pinfunction "-OUT_5") (pintype "passive"))
    )
    (net (code "50") (name "Net-(U11-EN)") (class "Default")
      (node (ref "R40") (pin "2") (pinfunction "2_2") (pintype "passive"))
      (node (ref "R42") (pin "1") (pinfunction "1_1") (pintype "passive"))
      (node (ref "U11") (pin "7") (pinfunction "EN_7") (pintype "passive"))
    )
    (net (code "51") (name "Net-(U11-V+)") (class "Default")
      (node (ref "C79") (pin "2") (pinfunction "2_2") (pintype "passive"))
      (node (ref "C80") (pin "2") (pinfunction "2_2") (pintype "passive"))
      (node (ref "C81") (pin "2") (pinfunction "2_2") (pintype "passive"))
      (node (ref "U11") (pin "3") (pinfunction "V+_3") (pintype "passive"))
    )
    (net (code "52") (name "Net-(U12-BYPASS)") (class "Default")
      (node (ref "C83") (pin "1") (pinfunction "1_1") (pintype "passive"))
      (node (ref "U12") (pin "4") (pinfunction "BYPASS_4") (pintype "bidirectional"))
    )
    (net (code "53") (name "Net-(U13-CAP+)") (class "Default")
      (node (ref "C87") (pin "1") (pinfunction "1_1") (pintype "passive"))
      (node (ref "U13") (pin "2") (pinfunction "CAP+_2") (pintype "passive"))
    )
    (net (code "54") (name "Net-(U13-CAP-)") (class "Default")
      (node (ref "C87") (pin "2") (pinfunction "2_2") (pintype "passive"))
      (node (ref "U13") (pin "4") (pinfunction "CAP-_4") (pintype "passive"))
    )
    (net (code "55") (name "Net-(U14-CAP+)") (class "Default")
      (node (ref "C88") (pin "1") (pinfunction "1_1") (pintype "passive"))
      (node (ref "U14") (pin "2") (pinfunction "CAP+_2") (pintype "passive"))
    )
    (net (code "56") (name "Net-(U14-CAP-)") (class "Default")
      (node (ref "C88") (pin "2") (pinfunction "2_2") (pintype "passive"))
      (node (ref "U14") (pin "4") (pinfunction "CAP-_4") (pintype "passive"))
    )
    (net (code "57") (name "Net-(U15-CAP+)") (class "Default")
      (node (ref "C89") (pin "1") (pinfunction "1_1") (pintype "passive"))
      (node (ref "U15") (pin "2") (pinfunction "CAP+_2") (pintype "passive"))
    )
    (net (code "58") (name "Net-(U15-CAP-)") (class "Default")
      (node (ref "C89") (pin "2") (pinfunction "2_2") (pintype "passive"))
      (node (ref "U15") (pin "4") (pinfunction "CAP-_4") (pintype "passive"))
    )
    (net (code "59") (name "Net-(U16-CAP+)") (class "Default")
      (node (ref "C90") (pin "1") (pinfunction "1_1") (pintype "passive"))
      (node (ref "U16") (pin "2") (pinfunction "CAP+_2") (pintype "passive"))
    )
    (net (code "60") (name "Net-(U16-CAP-)") (class "Default")
      (node (ref "C90") (pin "2") (pinfunction "2_2") (pintype "passive"))
      (node (ref "U16") (pin "4") (pinfunction "CAP-_4") (pintype "passive"))
    )
    (net (code "61") (name "Net-(U17-CAP+)") (class "Default")
      (node (ref "C91") (pin "1") (pinfunction "1_1") (pintype "passive"))
      (node (ref "U17") (pin "2") (pinfunction "CAP+_2") (pintype "passive"))
    )
    (net (code "62") (name "Net-(U17-CAP-)") (class "Default")
      (node (ref "C91") (pin "2") (pinfunction "2_2") (pintype "passive"))
      (node (ref "U17") (pin "4") (pinfunction "CAP-_4") (pintype "passive"))
    )
    (net (code "63") (name "unconnected-(U6-DNC_1-Pad1)") (class "Default")
      (node (ref "U6") (pin "1") (pinfunction "DNC_1_1") (pintype "passive+no_connect"))
    )
    (net (code "64") (name "unconnected-(U6-DNC_2-Pad8)") (class "Default")
      (node (ref "U6") (pin "8") (pinfunction "DNC_2_8") (pintype "passive+no_connect"))
    )
    (net (code "65") (name "unconnected-(U6-NIC_1-Pad3)") (class "Default")
      (node (ref "U6") (pin "3") (pinfunction "NIC_1_3") (pintype "passive+no_connect"))
    )
    (net (code "66") (name "unconnected-(U6-NIC_2-Pad7)") (class "Default")
      (node (ref "U6") (pin "7") (pinfunction "NIC_2_7") (pintype "passive+no_connect"))
    )
    (net (code "67") (name "unconnected-(U8-DNC-Pad8)") (class "Default")
      (node (ref "U8") (pin "8") (pinfunction "DNC_8") (pintype "passive+no_connect"))
    )
    (net (code "68") (name "unconnected-(U8-DNC_2-Pad7)") (class "Default")
      (node (ref "U8") (pin "7") (pinfunction "DNC_2_7") (pintype "passive+no_connect"))
    )
    (net (code "69") (name "unconnected-(U8-DNC_3-Pad6)") (class "Default")
      (node (ref "U8") (pin "6") (pinfunction "DNC_3_6") (pintype "passive+no_connect"))
    )
    (net (code "70") (name "unconnected-(U8-XOUT-Pad2)") (class "Default")
      (node (ref "U8") (pin "2") (pinfunction "XOUT_2") (pintype "output+no_connect"))
    )
    (net (code "71") (name "unconnected-(U13-OSC-Pad7)") (class "Default")
      (node (ref "U13") (pin "7") (pinfunction "OSC_7") (pintype "passive+no_connect"))
    )
    (net (code "72") (name "unconnected-(U13-SD-Pad1)") (class "Default")
      (node (ref "U13") (pin "1") (pinfunction "SD_1") (pintype "passive+no_connect"))
    )
    (net (code "73") (name "unconnected-(U14-OSC-Pad7)") (class "Default")
      (node (ref "U14") (pin "7") (pinfunction "OSC_7") (pintype "passive+no_connect"))
    )
    (net (code "74") (name "unconnected-(U14-SD-Pad1)") (class "Default")
      (node (ref "U14") (pin "1") (pinfunction "SD_1") (pintype "passive+no_connect"))
    )
    (net (code "75") (name "unconnected-(U15-OSC-Pad7)") (class "Default")
      (node (ref "U15") (pin "7") (pinfunction "OSC_7") (pintype "passive+no_connect"))
    )
    (net (code "76") (name "unconnected-(U15-SD-Pad1)") (class "Default")
      (node (ref "U15") (pin "1") (pinfunction "SD_1") (pintype "passive+no_connect"))
    )
    (net (code "77") (name "unconnected-(U16-OSC-Pad7)") (class "Default")
      (node (ref "U16") (pin "7") (pinfunction "OSC_7") (pintype "passive+no_connect"))
    )
    (net (code "78") (name "unconnected-(U16-SD-Pad1)") (class "Default")
      (node (ref "U16") (pin "1") (pinfunction "SD_1") (pintype "passive+no_connect"))
    )
    (net (code "79") (name "unconnected-(U17-OSC-Pad7)") (class "Default")
      (node (ref "U17") (pin "7") (pinfunction "OSC_7") (pintype "passive+no_connect"))
    )
    (net (code "80") (name "unconnected-(U17-SD-Pad1)") (class "Default")
      (node (ref "U17") (pin "1") (pinfunction "SD_1") (pintype "passive+no_connect"))
    )
  )
)
